# adapter1.net
KiCad netlist of a schematic drawn in EAGLE
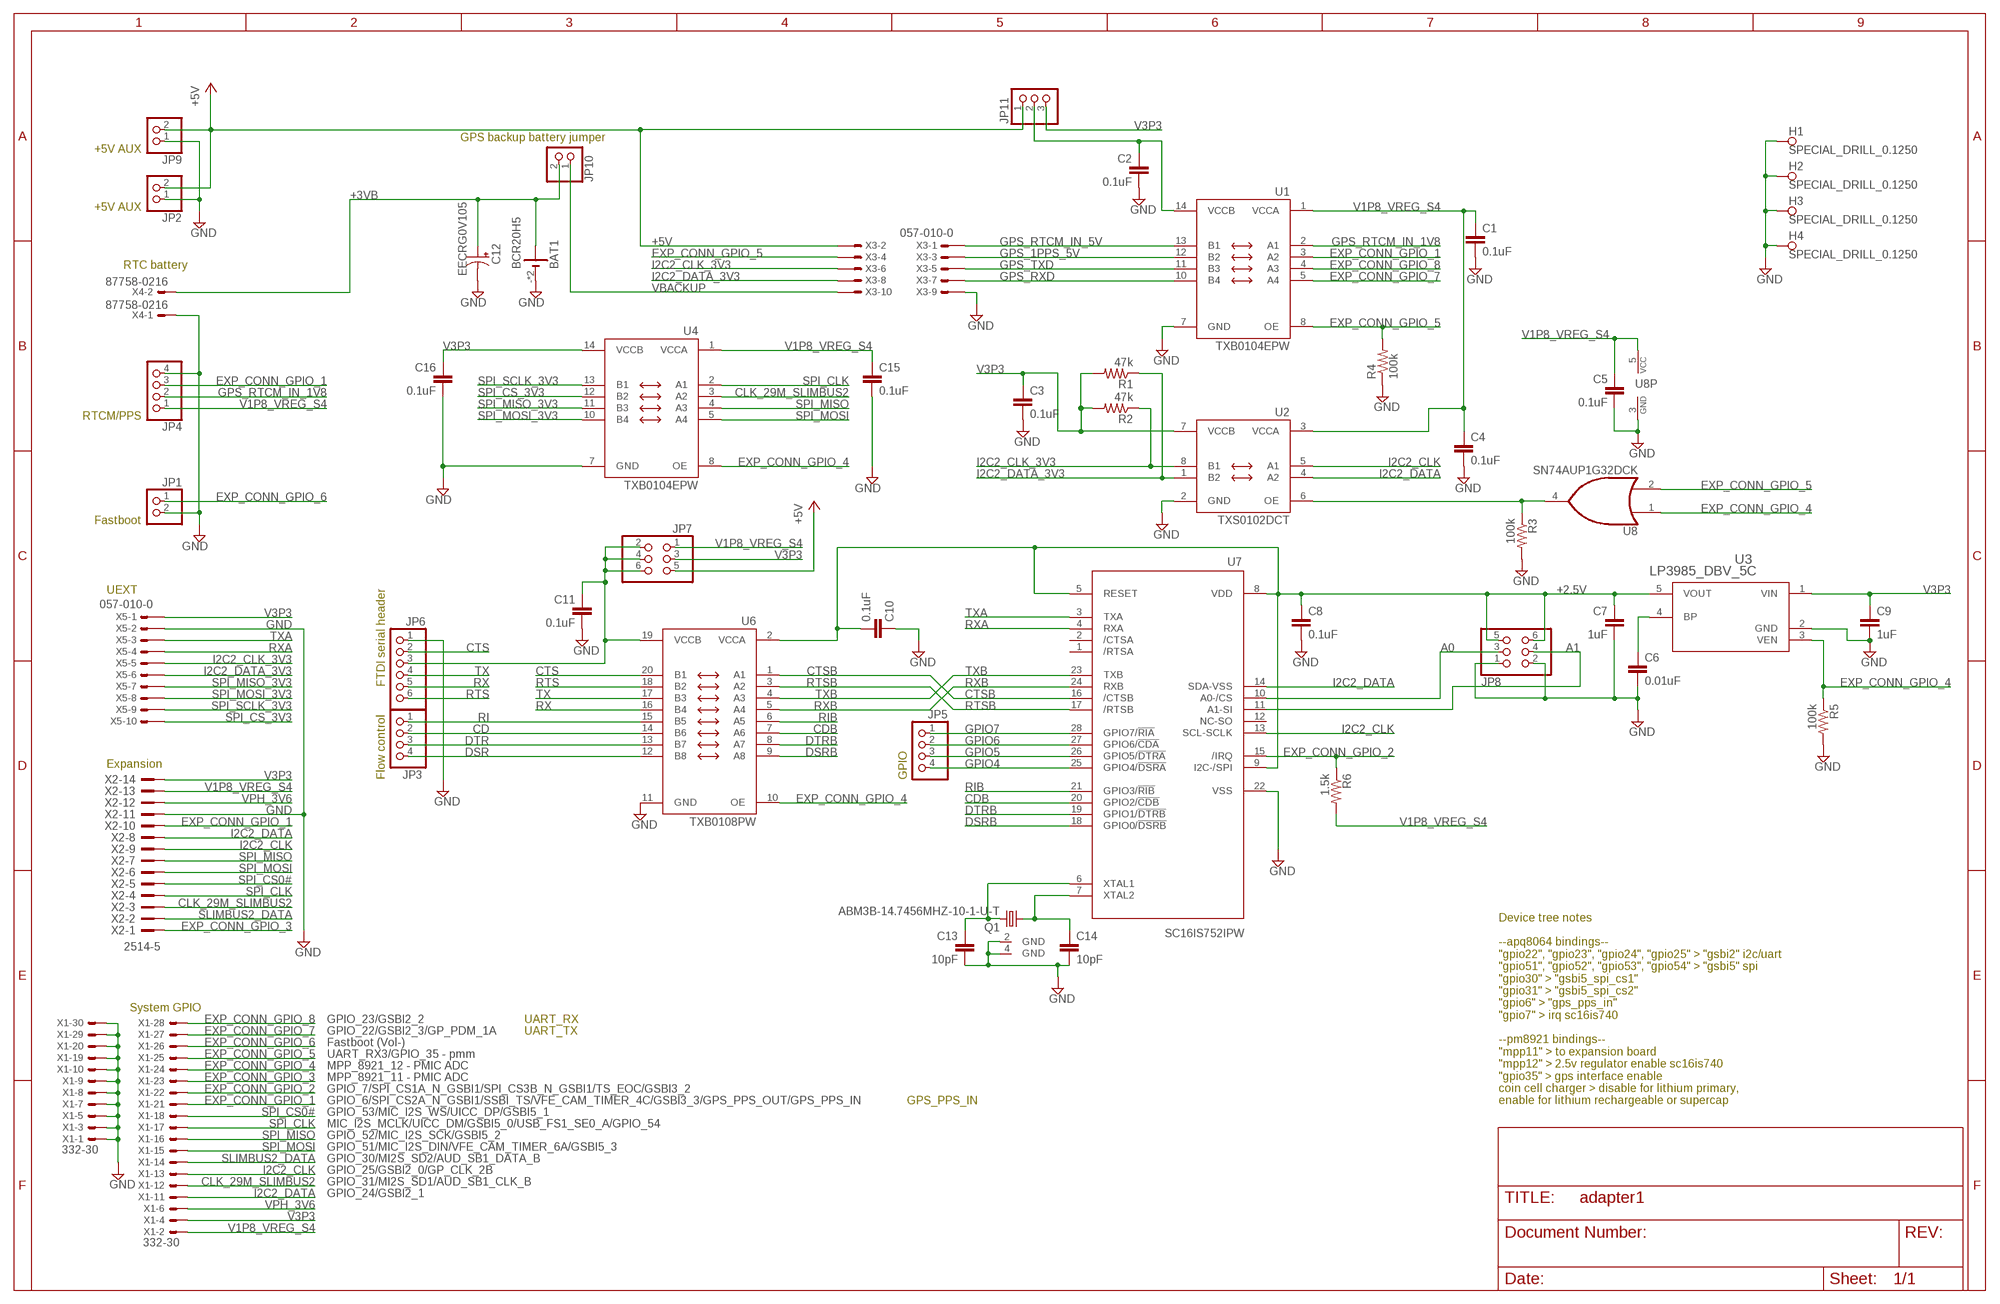
[diagram p0: schematic, sheet 1]

(export (version "E")
  (design (tool "Eeschema 10.0.6"))
  (components
    (comp (ref "BAT1")
      (value "BCR20H5")
      (footprint "eagle-import:BCR20H5_1066")
      (libsource (lib "eagle-import") (part "BCR20H5_1066"))
    )
    (comp (ref "C1")
      (value "0.1uF")
      (footprint "eagle-import:C0603")
      (libsource (lib "eagle-import") (part "C-EUC0603"))
    )
    (comp (ref "C2")
      (value "0.1uF")
      (footprint "eagle-import:C0603")
      (libsource (lib "eagle-import") (part "C-EUC0603"))
    )
    (comp (ref "C3")
      (value "0.1uF")
      (footprint "eagle-import:C0603")
      (libsource (lib "eagle-import") (part "C-EUC0603"))
    )
    (comp (ref "C4")
      (value "0.1uF")
      (footprint "eagle-import:C0603")
      (libsource (lib "eagle-import") (part "C-EUC0603"))
    )
    (comp (ref "C5")
      (value "0.1uF")
      (footprint "eagle-import:C0603")
      (libsource (lib "eagle-import") (part "C-EUC0603"))
    )
    (comp (ref "C6")
      (value "0.01uF")
      (footprint "eagle-import:C0603")
      (libsource (lib "eagle-import") (part "C-EUC0603"))
    )
    (comp (ref "C7")
      (value "1uF")
      (footprint "eagle-import:C0603")
      (libsource (lib "eagle-import") (part "C-EUC0603"))
    )
    (comp (ref "C8")
      (value "0.1uF")
      (footprint "eagle-import:C0603")
      (libsource (lib "eagle-import") (part "C-EUC0603"))
    )
    (comp (ref "C9")
      (value "1uF")
      (footprint "eagle-import:C0603")
      (libsource (lib "eagle-import") (part "C-EUC0603"))
    )
    (comp (ref "C10")
      (value "0.1uF")
      (footprint "eagle-import:C0603")
      (libsource (lib "eagle-import") (part "C-EUC0603"))
    )
    (comp (ref "C11")
      (value "0.1uF")
      (footprint "eagle-import:C0603")
      (libsource (lib "eagle-import") (part "C-EUC0603"))
    )
    (comp (ref "C12")
      (value "EECRG0V105")
      (footprint "eagle-import:EB20D")
      (libsource (lib "eagle-import") (part "CPOL-USE10-20"))
    )
    (comp (ref "C13")
      (value "10pF")
      (footprint "eagle-import:C0603")
      (libsource (lib "eagle-import") (part "C-EUC0603"))
    )
    (comp (ref "C14")
      (value "10pF")
      (footprint "eagle-import:C0603")
      (libsource (lib "eagle-import") (part "C-EUC0603"))
    )
    (comp (ref "C15")
      (value "0.1uF")
      (footprint "eagle-import:C0603")
      (libsource (lib "eagle-import") (part "C-EUC0603"))
    )
    (comp (ref "C16")
      (value "0.1uF")
      (footprint "eagle-import:C0603")
      (libsource (lib "eagle-import") (part "C-EUC0603"))
    )
    (comp (ref "H1")
      (value "SPECIAL_DRILL_0.1250")
      (footprint "eagle-import:PAD_0.1250")
      (libsource (lib "eagle-import") (part "SPECIAL_DRILL_0.1250"))
    )
    (comp (ref "H2")
      (value "SPECIAL_DRILL_0.1250")
      (footprint "eagle-import:PAD_0.1250")
      (libsource (lib "eagle-import") (part "SPECIAL_DRILL_0.1250"))
    )
    (comp (ref "H3")
      (value "SPECIAL_DRILL_0.1250")
      (footprint "eagle-import:PAD_0.1250")
      (libsource (lib "eagle-import") (part "SPECIAL_DRILL_0.1250"))
    )
    (comp (ref "H4")
      (value "SPECIAL_DRILL_0.1250")
      (footprint "eagle-import:PAD_0.1250")
      (libsource (lib "eagle-import") (part "SPECIAL_DRILL_0.1250"))
    )
    (comp (ref "JP1")
      (value "PINHD-1X2/90")
      (footprint "eagle-import:1X02_90")
      (libsource (lib "eagle-import") (part "PINHD-1X2/90"))
    )
    (comp (ref "JP2")
      (value "PINHD-1X2/90")
      (footprint "eagle-import:1X02_90")
      (libsource (lib "eagle-import") (part "PINHD-1X2/90"))
    )
    (comp (ref "JP3")
      (value "PINHD-1X4/90")
      (footprint "eagle-import:1X04_90")
      (libsource (lib "eagle-import") (part "PINHD-1X4/90"))
    )
    (comp (ref "JP4")
      (value "PINHD-1X4/90")
      (footprint "eagle-import:1X04_90")
      (libsource (lib "eagle-import") (part "PINHD-1X4/90"))
    )
    (comp (ref "JP5")
      (value "PINHD-1X4/90")
      (footprint "eagle-import:1X04_90")
      (libsource (lib "eagle-import") (part "PINHD-1X4/90"))
    )
    (comp (ref "JP6")
      (value "PINHD-1X6/90")
      (footprint "eagle-import:1X06_90")
      (libsource (lib "eagle-import") (part "PINHD-1X6/90"))
    )
    (comp (ref "JP7")
      (value "PINHD-2X3/90")
      (footprint "eagle-import:2X03_90")
      (libsource (lib "eagle-import") (part "PINHD-2X3/90"))
    )
    (comp (ref "JP8")
      (value "PINHD-2X3")
      (footprint "eagle-import:2X03")
      (libsource (lib "eagle-import") (part "PINHD-2X3"))
    )
    (comp (ref "JP9")
      (value "PINHD-1X2/90")
      (footprint "eagle-import:1X02_90")
      (libsource (lib "eagle-import") (part "PINHD-1X2/90"))
    )
    (comp (ref "JP10")
      (value "PINHD-1X2")
      (footprint "eagle-import:1X02")
      (libsource (lib "eagle-import") (part "PINHD-1X2"))
    )
    (comp (ref "JP11")
      (value "PINHD-1X3")
      (footprint "eagle-import:1X03")
      (libsource (lib "eagle-import") (part "PINHD-1X3"))
    )
    (comp (ref "Q1")
      (value "ABM3B-14.7456MHZ-10-1-U-T")
      (footprint "eagle-import:ABM3B")
      (libsource (lib "eagle-import") (part "C-SHIELDABM3B"))
    )
    (comp (ref "R1")
      (value "47k")
      (footprint "eagle-import:R0603")
      (libsource (lib "eagle-import") (part "R-US_R0603"))
    )
    (comp (ref "R2")
      (value "47k")
      (footprint "eagle-import:R0603")
      (libsource (lib "eagle-import") (part "R-US_R0603"))
    )
    (comp (ref "R3")
      (value "100k")
      (footprint "eagle-import:R0603")
      (libsource (lib "eagle-import") (part "R-US_R0603"))
    )
    (comp (ref "R4")
      (value "100k")
      (footprint "eagle-import:R0603")
      (libsource (lib "eagle-import") (part "R-US_R0603"))
    )
    (comp (ref "R5")
      (value "100k")
      (footprint "eagle-import:R0603")
      (libsource (lib "eagle-import") (part "R-US_R0603"))
    )
    (comp (ref "R6")
      (value "1.5k")
      (footprint "eagle-import:R0603")
      (libsource (lib "eagle-import") (part "R-US_R0603"))
    )
    (comp (ref "U1")
      (value "TXB0104EPW")
      (footprint "eagle-import:PW_R-PDSO-G14")
      (libsource (lib "eagle-import") (part "TXS0104EPW"))
    )
    (comp (ref "U2")
      (value "TXS0102DCT")
      (footprint "eagle-import:DCT_R-PDSO-G8")
      (libsource (lib "eagle-import") (part "TXS0102DCT"))
    )
    (comp (ref "U3")
      (value "LP3985_DBV_5C")
      (footprint "eagle-import:MF05A-M")
      (libsource (lib "eagle-import") (part "LP3985_DBV_5C"))
    )
    (comp (ref "U4")
      (value "TXB0104EPW")
      (footprint "eagle-import:PW_R-PDSO-G14")
      (libsource (lib "eagle-import") (part "TXS0104EPW"))
    )
    (comp (ref "U6")
      (value "TXB0108PW")
      (footprint "eagle-import:PW_R-PDSO-G20")
      (libsource (lib "eagle-import") (part "TXS0108PW"))
    )
    (comp (ref "U7")
      (value "SC16IS752IPW")
      (footprint "eagle-import:SSOP28")
      (libsource (lib "eagle-import") (part "SC16IS752IPW"))
    )
    (comp (ref "U8")
      (value "SN74AUP1G32DCK")
      (footprint "eagle-import:SC70-5")
      (libsource (lib "eagle-import") (part "741G32DCKAHC"))
    )
    (comp (ref "X1")
      (value "332-30")
      (footprint "eagle-import:332-30")
      (libsource (lib "eagle-import") (part "332-30"))
    )
    (comp (ref "X2")
      (value "2514-5")
      (footprint "eagle-import:PAK100_2500-5-14")
      (fields (field (name "MPN") "N2514-5002RB"))
      (libsource (lib "eagle-import") (part "2514-5"))
    )
    (comp (ref "X3")
      (value "057-010-0")
      (footprint "eagle-import:057-010-0")
      (libsource (lib "eagle-import") (part "057-010-0"))
    )
    (comp (ref "X4")
      (value "87758-0216")
      (footprint "eagle-import:87758-0216")
      (libsource (lib "eagle-import") (part "87758-0216"))
    )
    (comp (ref "X5")
      (value "057-010-0")
      (footprint "eagle-import:057-010-0")
      (libsource (lib "eagle-import") (part "057-010-0"))
    )
  )
  (nets
    (net (code "1") (name "+5V") (class "Default")
      (node (ref "JP11") (pin "1") (pinfunction "1_1") (pintype "passive"))
      (node (ref "JP2") (pin "2") (pinfunction "2_2") (pintype "passive"))
      (node (ref "JP7") (pin "5") (pinfunction "5_5") (pintype "passive"))
      (node (ref "JP9") (pin "2") (pinfunction "2_2") (pintype "passive"))
      (node (ref "X3") (pin "2") (pinfunction "S_2") (pintype "passive"))
    )
    (net (code "2") (name "/+2.5V") (class "Default")
      (node (ref "C10") (pin "2") (pinfunction "2_2") (pintype "passive"))
      (node (ref "C7") (pin "1") (pinfunction "1_1") (pintype "passive"))
      (node (ref "C8") (pin "1") (pinfunction "1_1") (pintype "passive"))
      (node (ref "JP8") (pin "5") (pinfunction "5_5") (pintype "passive"))
      (node (ref "JP8") (pin "6") (pinfunction "6_6") (pintype "passive"))
      (node (ref "U3") (pin "5") (pinfunction "VOUT_5") (pintype "output"))
      (node (ref "U6") (pin "2") (pinfunction "VCCA_2") (pintype "bidirectional"))
      (node (ref "U7") (pin "5") (pinfunction "RESET_5") (pintype "bidirectional"))
      (node (ref "U7") (pin "8") (pinfunction "VDD_8") (pintype "bidirectional"))
      (node (ref "U7") (pin "9") (pinfunction "I2C-/SPI_9") (pintype "bidirectional"))
    )
    (net (code "3") (name "/+3VB") (class "Default")
      (node (ref "BAT1") (pin "+") (pinfunction "+_+") (pintype "passive"))
      (node (ref "BAT1") (pin "+1") (pinfunction "+_+1") (pintype "passive"))
      (node (ref "C12") (pin "+") (pinfunction "+_+") (pintype "passive"))
      (node (ref "JP10") (pin "2") (pinfunction "2_2") (pintype "passive"))
      (node (ref "X4") (pin "2") (pinfunction "S_2") (pintype "passive"))
    )
    (net (code "4") (name "/A0") (class "Default")
      (node (ref "JP8") (pin "3") (pinfunction "3_3") (pintype "passive"))
      (node (ref "U7") (pin "10") (pinfunction "A0-/CS_10") (pintype "bidirectional"))
    )
    (net (code "5") (name "/A1") (class "Default")
      (node (ref "JP8") (pin "4") (pinfunction "4_4") (pintype "passive"))
      (node (ref "U7") (pin "11") (pinfunction "A1-SI_11") (pintype "bidirectional"))
    )
    (net (code "6") (name "/CD") (class "Default")
      (node (ref "JP3") (pin "2") (pinfunction "2_2") (pintype "passive"))
      (node (ref "U6") (pin "14") (pinfunction "B6_14") (pintype "bidirectional"))
    )
    (net (code "7") (name "/CDB") (class "Default")
      (node (ref "U6") (pin "7") (pinfunction "A6_7") (pintype "bidirectional"))
      (node (ref "U7") (pin "20") (pinfunction "GPIO2/~{CDB}_20") (pintype "bidirectional"))
    )
    (net (code "8") (name "/CLK_29M_SLIMBUS2") (class "Default")
      (node (ref "U4") (pin "3") (pinfunction "A2_3") (pintype "bidirectional"))
      (node (ref "X1") (pin "12") (pinfunction "S_12") (pintype "passive"))
      (node (ref "X2") (pin "3") (pinfunction "KL_3") (pintype "passive"))
    )
    (net (code "9") (name "/CTS") (class "Default")
      (node (ref "JP6") (pin "2") (pinfunction "2_2") (pintype "passive"))
      (node (ref "U6") (pin "20") (pinfunction "B1_20") (pintype "bidirectional"))
    )
    (net (code "10") (name "/CTSB") (class "Default")
      (node (ref "U6") (pin "1") (pinfunction "A1_1") (pintype "bidirectional"))
      (node (ref "U7") (pin "16") (pinfunction "/CTSB_16") (pintype "bidirectional"))
    )
    (net (code "11") (name "/DSR") (class "Default")
      (node (ref "JP3") (pin "4") (pinfunction "4_4") (pintype "passive"))
      (node (ref "U6") (pin "12") (pinfunction "B8_12") (pintype "bidirectional"))
    )
    (net (code "12") (name "/DSRB") (class "Default")
      (node (ref "U6") (pin "9") (pinfunction "A8_9") (pintype "bidirectional"))
      (node (ref "U7") (pin "18") (pinfunction "GPIO0/~{DSRB}_18") (pintype "bidirectional"))
    )
    (net (code "13") (name "/DTR") (class "Default")
      (node (ref "JP3") (pin "3") (pinfunction "3_3") (pintype "passive"))
      (node (ref "U6") (pin "13") (pinfunction "B7_13") (pintype "bidirectional"))
    )
    (net (code "14") (name "/DTRB") (class "Default")
      (node (ref "U6") (pin "8") (pinfunction "A7_8") (pintype "bidirectional"))
      (node (ref "U7") (pin "19") (pinfunction "GPIO1/~{DTRB}_19") (pintype "bidirectional"))
    )
    (net (code "15") (name "/EXP_CONN_GPIO_1") (class "Default")
      (node (ref "JP4") (pin "3") (pinfunction "3_3") (pintype "passive"))
      (node (ref "U1") (pin "3") (pinfunction "A2_3") (pintype "bidirectional"))
      (node (ref "X1") (pin "21") (pinfunction "S_21") (pintype "passive"))
      (node (ref "X2") (pin "10") (pinfunction "KL_10") (pintype "passive"))
    )
    (net (code "16") (name "/EXP_CONN_GPIO_2") (class "Default")
      (node (ref "R6") (pin "1") (pinfunction "1_1") (pintype "passive"))
      (node (ref "U7") (pin "15") (pinfunction "/IRQ_15") (pintype "bidirectional"))
      (node (ref "X1") (pin "22") (pinfunction "S_22") (pintype "passive"))
    )
    (net (code "17") (name "/EXP_CONN_GPIO_3") (class "Default")
      (node (ref "X1") (pin "23") (pinfunction "S_23") (pintype "passive"))
      (node (ref "X2") (pin "1") (pinfunction "KL_1") (pintype "passive"))
    )
    (net (code "18") (name "/EXP_CONN_GPIO_4") (class "Default")
      (node (ref "R5") (pin "1") (pinfunction "1_1") (pintype "passive"))
      (node (ref "U3") (pin "3") (pinfunction "VEN_3") (pintype "passive"))
      (node (ref "U4") (pin "8") (pinfunction "OE_8") (pintype "bidirectional"))
      (node (ref "U6") (pin "10") (pinfunction "OE_10") (pintype "bidirectional"))
      (node (ref "U8") (pin "1") (pinfunction "I0_1") (pintype "input"))
      (node (ref "X1") (pin "24") (pinfunction "S_24") (pintype "passive"))
    )
    (net (code "19") (name "/EXP_CONN_GPIO_5") (class "Default")
      (node (ref "R4") (pin "2") (pinfunction "2_2") (pintype "passive"))
      (node (ref "U1") (pin "8") (pinfunction "OE_8") (pintype "bidirectional"))
      (node (ref "U8") (pin "2") (pinfunction "I1_2") (pintype "input"))
      (node (ref "X1") (pin "25") (pinfunction "S_25") (pintype "passive"))
      (node (ref "X3") (pin "4") (pinfunction "S_4") (pintype "passive"))
    )
    (net (code "20") (name "/EXP_CONN_GPIO_6") (class "Default")
      (node (ref "JP1") (pin "1") (pinfunction "1_1") (pintype "passive"))
      (node (ref "X1") (pin "26") (pinfunction "S_26") (pintype "passive"))
    )
    (net (code "21") (name "/EXP_CONN_GPIO_7") (class "Default")
      (node (ref "U1") (pin "5") (pinfunction "A4_5") (pintype "bidirectional"))
      (node (ref "X1") (pin "27") (pinfunction "S_27") (pintype "passive"))
    )
    (net (code "22") (name "/EXP_CONN_GPIO_8") (class "Default")
      (node (ref "U1") (pin "4") (pinfunction "A3_4") (pintype "bidirectional"))
      (node (ref "X1") (pin "28") (pinfunction "S_28") (pintype "passive"))
    )
    (net (code "23") (name "/GPIO4") (class "Default")
      (node (ref "JP5") (pin "4") (pinfunction "4_4") (pintype "passive"))
      (node (ref "U7") (pin "25") (pinfunction "GPIO4/~{DSRA}_25") (pintype "bidirectional"))
    )
    (net (code "24") (name "/GPIO5") (class "Default")
      (node (ref "JP5") (pin "3") (pinfunction "3_3") (pintype "passive"))
      (node (ref "U7") (pin "26") (pinfunction "GPIO5/~{DTRA}_26") (pintype "bidirectional"))
    )
    (net (code "25") (name "/GPIO6") (class "Default")
      (node (ref "JP5") (pin "2") (pinfunction "2_2") (pintype "passive"))
      (node (ref "U7") (pin "27") (pinfunction "GPIO6/~{CDA}_27") (pintype "bidirectional"))
    )
    (net (code "26") (name "/GPIO7") (class "Default")
      (node (ref "JP5") (pin "1") (pinfunction "1_1") (pintype "passive"))
      (node (ref "U7") (pin "28") (pinfunction "GPIO7/~{RIA}_28") (pintype "bidirectional"))
    )
    (net (code "27") (name "/GPS_1PPS_5V") (class "Default")
      (node (ref "U1") (pin "12") (pinfunction "B2_12") (pintype "bidirectional"))
      (node (ref "X3") (pin "3") (pinfunction "S_3") (pintype "passive"))
    )
    (net (code "28") (name "/GPS_RTCM_IN_1V8") (class "Default")
      (node (ref "JP4") (pin "2") (pinfunction "2_2") (pintype "passive"))
      (node (ref "U1") (pin "2") (pinfunction "A1_2") (pintype "bidirectional"))
    )
    (net (code "29") (name "/GPS_RTCM_IN_5V") (class "Default")
      (node (ref "U1") (pin "13") (pinfunction "B1_13") (pintype "bidirectional"))
      (node (ref "X3") (pin "1") (pinfunction "S_1") (pintype "passive"))
    )
    (net (code "30") (name "/GPS_RXD") (class "Default")
      (node (ref "U1") (pin "10") (pinfunction "B4_10") (pintype "bidirectional"))
      (node (ref "X3") (pin "7") (pinfunction "S_7") (pintype "passive"))
    )
    (net (code "31") (name "/GPS_TXD") (class "Default")
      (node (ref "U1") (pin "11") (pinfunction "B3_11") (pintype "bidirectional"))
      (node (ref "X3") (pin "5") (pinfunction "S_5") (pintype "passive"))
    )
    (net (code "32") (name "/I2C2_CLK") (class "Default")
      (node (ref "U2") (pin "5") (pinfunction "A1_5") (pintype "bidirectional"))
      (node (ref "U7") (pin "13") (pinfunction "SCL-SCLK_13") (pintype "bidirectional"))
      (node (ref "X1") (pin "13") (pinfunction "S_13") (pintype "passive"))
      (node (ref "X2") (pin "9") (pinfunction "KL_9") (pintype "passive"))
    )
    (net (code "33") (name "/I2C2_CLK_3V3") (class "Default")
      (node (ref "R2") (pin "1") (pinfunction "1_1") (pintype "passive"))
      (node (ref "U2") (pin "8") (pinfunction "B1_8") (pintype "bidirectional"))
      (node (ref "X3") (pin "6") (pinfunction "S_6") (pintype "passive"))
      (node (ref "X5") (pin "5") (pinfunction "S_5") (pintype "passive"))
    )
    (net (code "34") (name "/I2C2_DATA") (class "Default")
      (node (ref "U2") (pin "4") (pinfunction "A2_4") (pintype "bidirectional"))
      (node (ref "U7") (pin "14") (pinfunction "SDA-VSS_14") (pintype "bidirectional"))
      (node (ref "X1") (pin "11") (pinfunction "S_11") (pintype "passive"))
      (node (ref "X2") (pin "8") (pinfunction "KL_8") (pintype "passive"))
    )
    (net (code "35") (name "/I2C2_DATA_3V3") (class "Default")
      (node (ref "R1") (pin "1") (pinfunction "1_1") (pintype "passive"))
      (node (ref "U2") (pin "1") (pinfunction "B2_1") (pintype "bidirectional"))
      (node (ref "X3") (pin "8") (pinfunction "S_8") (pintype "passive"))
      (node (ref "X5") (pin "6") (pinfunction "S_6") (pintype "passive"))
    )
    (net (code "36") (name "/RI") (class "Default")
      (node (ref "JP3") (pin "1") (pinfunction "1_1") (pintype "passive"))
      (node (ref "U6") (pin "15") (pinfunction "B5_15") (pintype "bidirectional"))
    )
    (net (code "37") (name "/RIB") (class "Default")
      (node (ref "U6") (pin "6") (pinfunction "A5_6") (pintype "bidirectional"))
      (node (ref "U7") (pin "21") (pinfunction "GPIO3/~{RIB}_21") (pintype "bidirectional"))
    )
    (net (code "38") (name "/RTS") (class "Default")
      (node (ref "JP6") (pin "6") (pinfunction "6_6") (pintype "passive"))
      (node (ref "U6") (pin "18") (pinfunction "B2_18") (pintype "bidirectional"))
    )
    (net (code "39") (name "/RTSB") (class "Default")
      (node (ref "U6") (pin "3") (pinfunction "A2_3") (pintype "bidirectional"))
      (node (ref "U7") (pin "17") (pinfunction "/RTSB_17") (pintype "bidirectional"))
    )
    (net (code "40") (name "/RX") (class "Default")
      (node (ref "JP6") (pin "5") (pinfunction "5_5") (pintype "passive"))
      (node (ref "U6") (pin "16") (pinfunction "B4_16") (pintype "bidirectional"))
    )
    (net (code "41") (name "/RXA") (class "Default")
      (node (ref "U7") (pin "4") (pinfunction "RXA_4") (pintype "bidirectional"))
      (node (ref "X5") (pin "4") (pinfunction "S_4") (pintype "passive"))
    )
    (net (code "42") (name "/RXB") (class "Default")
      (node (ref "U6") (pin "5") (pinfunction "A4_5") (pintype "bidirectional"))
      (node (ref "U7") (pin "24") (pinfunction "RXB_24") (pintype "bidirectional"))
    )
    (net (code "43") (name "/SLIMBUS2_DATA") (class "Default")
      (node (ref "X1") (pin "14") (pinfunction "S_14") (pintype "passive"))
      (node (ref "X2") (pin "2") (pinfunction "KL_2") (pintype "passive"))
    )
    (net (code "44") (name "/SPI_CLK") (class "Default")
      (node (ref "U4") (pin "2") (pinfunction "A1_2") (pintype "bidirectional"))
      (node (ref "X1") (pin "17") (pinfunction "S_17") (pintype "passive"))
      (node (ref "X2") (pin "4") (pinfunction "KL_4") (pintype "passive"))
    )
    (net (code "45") (name "/SPI_CS0#") (class "Default")
      (node (ref "X1") (pin "18") (pinfunction "S_18") (pintype "passive"))
      (node (ref "X2") (pin "5") (pinfunction "KL_5") (pintype "passive"))
    )
    (net (code "46") (name "/SPI_CS_3V3") (class "Default")
      (node (ref "U4") (pin "12") (pinfunction "B2_12") (pintype "bidirectional"))
      (node (ref "X5") (pin "10") (pinfunction "S_10") (pintype "passive"))
    )
    (net (code "47") (name "/SPI_MISO") (class "Default")
      (node (ref "U4") (pin "4") (pinfunction "A3_4") (pintype "bidirectional"))
      (node (ref "X1") (pin "16") (pinfunction "S_16") (pintype "passive"))
      (node (ref "X2") (pin "7") (pinfunction "KL_7") (pintype "passive"))
    )
    (net (code "48") (name "/SPI_MISO_3V3") (class "Default")
      (node (ref "U4") (pin "11") (pinfunction "B3_11") (pintype "bidirectional"))
      (node (ref "X5") (pin "7") (pinfunction "S_7") (pintype "passive"))
    )
    (net (code "49") (name "/SPI_MOSI") (class "Default")
      (node (ref "U4") (pin "5") (pinfunction "A4_5") (pintype "bidirectional"))
      (node (ref "X1") (pin "15") (pinfunction "S_15") (pintype "passive"))
      (node (ref "X2") (pin "6") (pinfunction "KL_6") (pintype "passive"))
    )
    (net (code "50") (name "/SPI_MOSI_3V3") (class "Default")
      (node (ref "U4") (pin "10") (pinfunction "B4_10") (pintype "bidirectional"))
      (node (ref "X5") (pin "8") (pinfunction "S_8") (pintype "passive"))
    )
    (net (code "51") (name "/SPI_SCLK_3V3") (class "Default")
      (node (ref "U4") (pin "13") (pinfunction "B1_13") (pintype "bidirectional"))
      (node (ref "X5") (pin "9") (pinfunction "S_9") (pintype "passive"))
    )
    (net (code "52") (name "/TX") (class "Default")
      (node (ref "JP6") (pin "4") (pinfunction "4_4") (pintype "passive"))
      (node (ref "U6") (pin "17") (pinfunction "B3_17") (pintype "bidirectional"))
    )
    (net (code "53") (name "/TXA") (class "Default")
      (node (ref "U7") (pin "3") (pinfunction "TXA_3") (pintype "bidirectional"))
      (node (ref "X5") (pin "3") (pinfunction "S_3") (pintype "passive"))
    )
    (net (code "54") (name "/TXB") (class "Default")
      (node (ref "U6") (pin "4") (pinfunction "A3_4") (pintype "bidirectional"))
      (node (ref "U7") (pin "23") (pinfunction "TXB_23") (pintype "bidirectional"))
    )
    (net (code "55") (name "/V1P8_VREG_S4") (class "Default")
      (node (ref "C1") (pin "1") (pinfunction "1_1") (pintype "passive"))
      (node (ref "C15") (pin "1") (pinfunction "1_1") (pintype "passive"))
      (node (ref "C4") (pin "1") (pinfunction "1_1") (pintype "passive"))
      (node (ref "C5") (pin "1") (pinfunction "1_1") (pintype "passive"))
      (node (ref "JP4") (pin "1") (pinfunction "1_1") (pintype "passive"))
      (node (ref "JP7") (pin "1") (pinfunction "1_1") (pintype "passive"))
      (node (ref "R6") (pin "2") (pinfunction "2_2") (pintype "passive"))
      (node (ref "U1") (pin "1") (pinfunction "VCCA_1") (pintype "bidirectional"))
      (node (ref "U2") (pin "3") (pinfunction "VCCA_3") (pintype "bidirectional"))
      (node (ref "U4") (pin "1") (pinfunction "VCCA_1") (pintype "bidirectional"))
      (node (ref "U8") (pin "5") (pinfunction "VCC_5") (pintype "power_in"))
      (node (ref "X1") (pin "2") (pinfunction "S_2") (pintype "passive"))
      (node (ref "X2") (pin "13") (pinfunction "KL_13") (pintype "passive"))
    )
    (net (code "56") (name "/V3P3") (class "Default")
      (node (ref "C16") (pin "1") (pinfunction "1_1") (pintype "passive"))
      (node (ref "C3") (pin "1") (pinfunction "1_1") (pintype "passive"))
      (node (ref "C9") (pin "1") (pinfunction "1_1") (pintype "passive"))
      (node (ref "JP11") (pin "3") (pinfunction "3_3") (pintype "passive"))
      (node (ref "JP7") (pin "3") (pinfunction "3_3") (pintype "passive"))
      (node (ref "R1") (pin "2") (pinfunction "2_2") (pintype "passive"))
      (node (ref "R2") (pin "2") (pinfunction "2_2") (pintype "passive"))
      (node (ref "U2") (pin "7") (pinfunction "VCCB_7") (pintype "bidirectional"))
      (node (ref "U3") (pin "1") (pinfunction "VIN_1") (pintype "input"))
      (node (ref "U4") (pin "14") (pinfunction "VCCB_14") (pintype "bidirectional"))
      (node (ref "X1") (pin "4") (pinfunction "S_4") (pintype "passive"))
      (node (ref "X2") (pin "14") (pinfunction "KL_14") (pintype "passive"))
      (node (ref "X5") (pin "1") (pinfunction "S_1") (pintype "passive"))
    )
    (net (code "57") (name "/VBACKUP") (class "Default")
      (node (ref "JP10") (pin "1") (pinfunction "1_1") (pintype "passive"))
      (node (ref "X3") (pin "10") (pinfunction "S_10") (pintype "passive"))
    )
    (net (code "58") (name "/VPH_3V6") (class "Default")
      (node (ref "X1") (pin "6") (pinfunction "S_6") (pintype "passive"))
      (node (ref "X2") (pin "12") (pinfunction "KL_12") (pintype "passive"))
    )
    (net (code "59") (name "GND") (class "Default")
      (node (ref "BAT1") (pin "-") (pinfunction "-_-") (pintype "passive"))
      (node (ref "BAT1") (pin "-1") (pinfunction "-_-1") (pintype "passive"))
      (node (ref "C1") (pin "2") (pinfunction "2_2") (pintype "passive"))
      (node (ref "C10") (pin "1") (pinfunction "1_1") (pintype "passive"))
      (node (ref "C11") (pin "2") (pinfunction "2_2") (pintype "passive"))
      (node (ref "C12") (pin "-") (pinfunction "-_-") (pintype "passive"))
      (node (ref "C13") (pin "2") (pinfunction "2_2") (pintype "passive"))
      (node (ref "C14") (pin "2") (pinfunction "2_2") (pintype "passive"))
      (node (ref "C15") (pin "2") (pinfunction "2_2") (pintype "passive"))
      (node (ref "C16") (pin "2") (pinfunction "2_2") (pintype "passive"))
      (node (ref "C2") (pin "2") (pinfunction "2_2") (pintype "passive"))
      (node (ref "C3") (pin "2") (pinfunction "2_2") (pintype "passive"))
      (node (ref "C4") (pin "2") (pinfunction "2_2") (pintype "passive"))
      (node (ref "C5") (pin "2") (pinfunction "2_2") (pintype "passive"))
      (node (ref "C6") (pin "2") (pinfunction "2_2") (pintype "passive"))
      (node (ref "C7") (pin "2") (pinfunction "2_2") (pintype "passive"))
      (node (ref "C8") (pin "2") (pinfunction "2_2") (pintype "passive"))
      (node (ref "C9") (pin "2") (pinfunction "2_2") (pintype "passive"))
      (node (ref "H1") (pin "1") (pinfunction "1_1") (pintype "passive"))
      (node (ref "H2") (pin "1") (pinfunction "1_1") (pintype "passive"))
      (node (ref "H3") (pin "1") (pinfunction "1_1") (pintype "passive"))
      (node (ref "H4") (pin "1") (pinfunction "1_1") (pintype "passive"))
      (node (ref "JP1") (pin "2") (pinfunction "2_2") (pintype "passive"))
      (node (ref "JP2") (pin "1") (pinfunction "1_1") (pintype "passive"))
      (node (ref "JP4") (pin "4") (pinfunction "4_4") (pintype "passive"))
      (node (ref "JP6") (pin "1") (pinfunction "1_1") (pintype "passive"))
      (node (ref "JP8") (pin "1") (pinfunction "1_1") (pintype "passive"))
      (node (ref "JP8") (pin "2") (pinfunction "2_2") (pintype "passive"))
      (node (ref "JP9") (pin "1") (pinfunction "1_1") (pintype "passive"))
      (node (ref "Q1") (pin "2") (pinfunction "GND_2") (pintype "bidirectional"))
      (node (ref "Q1") (pin "4") (pinfunction "GND_4") (pintype "bidirectional"))
      (node (ref "R3") (pin "2") (pinfunction "2_2") (pintype "passive"))
      (node (ref "R4") (pin "1") (pinfunction "1_1") (pintype "passive"))
      (node (ref "R5") (pin "2") (pinfunction "2_2") (pintype "passive"))
      (node (ref "U1") (pin "7") (pinfunction "GND_7") (pintype "bidirectional"))
      (node (ref "U2") (pin "2") (pinfunction "GND_2") (pintype "bidirectional"))
      (node (ref "U3") (pin "2") (pinfunction "GND_2") (pintype "passive"))
      (node (ref "U4") (pin "7") (pinfunction "GND_7") (pintype "bidirectional"))
      (node (ref "U6") (pin "11") (pinfunction "GND_11") (pintype "bidirectional"))
      (node (ref "U7") (pin "22") (pinfunction "VSS_22") (pintype "bidirectional"))
      (node (ref "U8") (pin "3") (pinfunction "GND_3") (pintype "power_in"))
      (node (ref "X1") (pin "1") (pinfunction "S_1") (pintype "passive"))
      (node (ref "X1") (pin "10") (pinfunction "S_10") (pintype "passive"))
      (node (ref "X1") (pin "19") (pinfunction "S_19") (pintype "passive"))
      (node (ref "X1") (pin "20") (pinfunction "S_20") (pintype "passive"))
      (node (ref "X1") (pin "29") (pinfunction "S_29") (pintype "passive"))
      (node (ref "X1") (pin "3") (pinfunction "S_3") (pintype "passive"))
      (node (ref "X1") (pin "30") (pinfunction "S_30") (pintype "passive"))
      (node (ref "X1") (pin "5") (pinfunction "S_5") (pintype "passive"))
      (node (ref "X1") (pin "7") (pinfunction "S_7") (pintype "passive"))
      (node (ref "X1") (pin "8") (pinfunction "S_8") (pintype "passive"))
      (node (ref "X1") (pin "9") (pinfunction "S_9") (pintype "passive"))
      (node (ref "X2") (pin "11") (pinfunction "KL_11") (pintype "passive"))
      (node (ref "X3") (pin "9") (pinfunction "S_9") (pintype "passive"))
      (node (ref "X4") (pin "1") (pinfunction "S_1") (pintype "passive"))
      (node (ref "X5") (pin "2") (pinfunction "S_2") (pintype "passive"))
    )
    (net (code "60") (name "Net-(Q1-2)") (class "Default")
      (node (ref "C14") (pin "1") (pinfunction "1_1") (pintype "passive"))
      (node (ref "Q1") (pin "3") (pinfunction "2_3") (pintype "passive"))
      (node (ref "U7") (pin "7") (pinfunction "XTAL2_7") (pintype "bidirectional"))
    )
    (net (code "61") (name "Net-(U1-VCCB)") (class "Default")
      (node (ref "C2") (pin "1") (pinfunction "1_1") (pintype "passive"))
      (node (ref "JP11") (pin "2") (pinfunction "2_2") (pintype "passive"))
      (node (ref "U1") (pin "14") (pinfunction "VCCB_14") (pintype "bidirectional"))
    )
    (net (code "62") (name "Net-(U2-OE)") (class "Default")
      (node (ref "R3") (pin "1") (pinfunction "1_1") (pintype "passive"))
      (node (ref "U2") (pin "6") (pinfunction "OE_6") (pintype "bidirectional"))
      (node (ref "U8") (pin "4") (pinfunction "O_4") (pintype "output"))
    )
    (net (code "63") (name "Net-(U3-BP)") (class "Default")
      (node (ref "C6") (pin "1") (pinfunction "1_1") (pintype "passive"))
      (node (ref "U3") (pin "4") (pinfunction "BP_4") (pintype "passive"))
    )
    (net (code "64") (name "Net-(U6-VCCB)") (class "Default")
      (node (ref "C11") (pin "1") (pinfunction "1_1") (pintype "passive"))
      (node (ref "JP6") (pin "3") (pinfunction "3_3") (pintype "passive"))
      (node (ref "JP7") (pin "2") (pinfunction "2_2") (pintype "passive"))
      (node (ref "JP7") (pin "4") (pinfunction "4_4") (pintype "passive"))
      (node (ref "JP7") (pin "6") (pinfunction "6_6") (pintype "passive"))
      (node (ref "U6") (pin "19") (pinfunction "VCCB_19") (pintype "bidirectional"))
    )
    (net (code "65") (name "Net-(U7-XTAL1)") (class "Default")
      (node (ref "C13") (pin "1") (pinfunction "1_1") (pintype "passive"))
      (node (ref "Q1") (pin "1") (pinfunction "1_1") (pintype "passive"))
      (node (ref "U7") (pin "6") (pinfunction "XTAL1_6") (pintype "bidirectional"))
    )
    (net (code "66") (name "unconnected-(U7-NC-SO-Pad12)") (class "Default")
      (node (ref "U7") (pin "12") (pinfunction "NC-SO_12") (pintype "bidirectional"))
    )
    (net (code "67") (name "unconnected-(U7-{slash}CTSA-Pad2)") (class "Default")
      (node (ref "U7") (pin "2") (pinfunction "/CTSA_2") (pintype "bidirectional"))
    )
    (net (code "68") (name "unconnected-(U7-{slash}RTSA-Pad1)") (class "Default")
      (node (ref "U7") (pin "1") (pinfunction "/RTSA_1") (pintype "bidirectional"))
    )
  )
)
